# Power_PD.net
KiCad netlist of a schematic drawn in Altium Designer
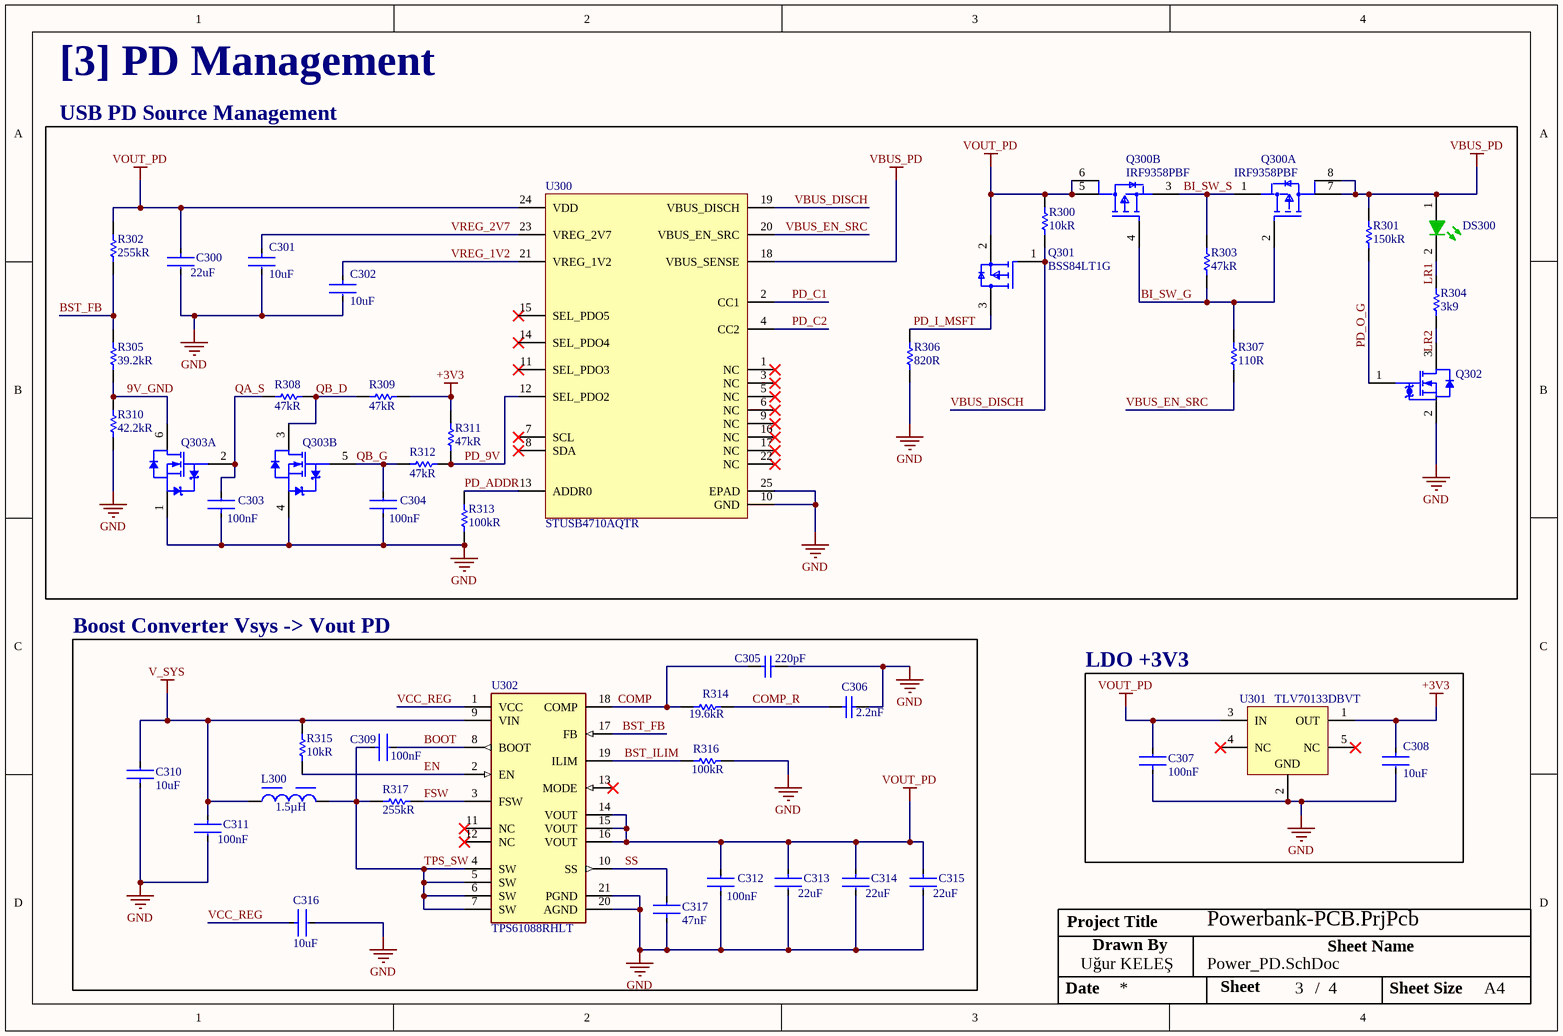
[diagram p0: Power_PD.SchDoc]

(export (version "E")
  (design (tool "Eeschema 10.0.6"))
  (components
    (comp (ref "C300")
      (value "GRT21BR61E226ME13L")
      (footprint "FP-GRT21B-0_2-IPC_C")
      (description "Multi-Layer Ceramic Capacitor 22uF 25V X5R ±20% 0805 Emboss T/R")
      (fields (field (name "CAPACITANCE") "22uF") (field (name "TOLERANCE") "20%"))
      (libsource (lib "Altium Content Vault") (part "02cd4be3c70576c341d710602a673aa"))
    )
    (comp (ref "C301")
      (value "GRM188R61E106MA73D")
      (footprint "FP-GRM188-0_2-MFG")
      (description "Chip Multilayer Ceramic Capacitors for General Purpose, 0603, 10uF, X5R, 15%, 20%, 25V")
      (fields
        (field (name "TOLERANCE") "20%")
        (field (name "VOLTAGE") "25V")
        (field (name "CAPACITANCE") "10uF")
      )
      (libsource (lib "Altium Content Vault") (part "11868f565c42a9108669ba33697ecf6"))
    )
    (comp (ref "C302")
      (value "GRM188R61E106MA73D")
      (footprint "FP-GRM188-0_2-MFG")
      (description "Chip Multilayer Ceramic Capacitors for General Purpose, 0603, 10uF, X5R, 15%, 20%, 25V")
      (fields
        (field (name "TOLERANCE") "20%")
        (field (name "VOLTAGE") "25V")
        (field (name "CAPACITANCE") "10uF")
      )
      (libsource (lib "Altium Content Vault") (part "11868f565c42a9108669ba33697ecf6"))
    )
    (comp (ref "C303")
      (value "GRM155R61H104KE19D")
      (footprint "FP-GRM155-0_05-IPC_A")
      (description "Chip Multilayer Ceramic Capacitors for General Purpose, 0402, 0.10uF, X5R, 15%, 10%, 50V")
      (fields
        (field (name "VOLTAGE") "50V")
        (field (name "TOLERANCE") "10%")
        (field (name "CAPACITANCE") "100nF")
      )
      (libsource (lib "Altium Content Vault") (part "02cd4be3c70576c341d710602a673aa"))
    )
    (comp (ref "C304")
      (value "GRM155R61H104KE19D")
      (footprint "FP-GRM155-0_05-IPC_A")
      (description "Chip Multilayer Ceramic Capacitors for General Purpose, 0402, 0.10uF, X5R, 15%, 10%, 50V")
      (fields
        (field (name "VOLTAGE") "50V")
        (field (name "TOLERANCE") "10%")
        (field (name "CAPACITANCE") "100nF")
      )
      (libsource (lib "Altium Content Vault") (part "02cd4be3c70576c341d710602a673aa"))
    )
    (comp (ref "C305")
      (value "220pF")
      (footprint "CAPC1005X55X25LL05T10")
      (fields (field (name "MANUFACTURER") "Murata") (field (name "PART NUMBER") "GRM155R71H221KA01D"))
      (libsource (lib "Altium Content Vault") (part "CAP"))
    )
    (comp (ref "C306")
      (value "2.2nF")
      (footprint "CAPC1005X55X25LL05T10")
      (fields (field (name "PART NUMBER") "GRM155R71E222KA01D") (field (name "MANUFACTURER") "Murata"))
      (libsource (lib "Altium Content Vault") (part "CAP"))
    )
    (comp (ref "C307")
      (value "GRM155R61H104KE19D")
      (footprint "FP-GRM155-0_05-IPC_A")
      (description "Chip Multilayer Ceramic Capacitors for General Purpose, 0402, 0.10uF, X5R, 15%, 10%, 50V")
      (fields
        (field (name "VOLTAGE") "50V")
        (field (name "TOLERANCE") "10%")
        (field (name "CAPACITANCE") "100nF")
      )
      (libsource (lib "Altium Content Vault") (part "02cd4be3c70576c341d710602a673aa"))
    )
    (comp (ref "C308")
      (value "GRM188R61E106MA73D")
      (footprint "FP-GRM188-0_2-MFG")
      (description "Chip Multilayer Ceramic Capacitors for General Purpose, 0603, 10uF, X5R, 15%, 20%, 25V")
      (fields
        (field (name "TOLERANCE") "20%")
        (field (name "VOLTAGE") "25V")
        (field (name "CAPACITANCE") "10uF")
      )
      (libsource (lib "Altium Content Vault") (part "11868f565c42a9108669ba33697ecf6"))
    )
    (comp (ref "C309")
      (value "GRM155R61H104KE19D")
      (footprint "FP-GRM155-0_05-IPC_A")
      (description "Chip Multilayer Ceramic Capacitors for General Purpose, 0402, 0.10uF, X5R, 15%, 10%, 50V")
      (fields
        (field (name "VOLTAGE") "50V")
        (field (name "TOLERANCE") "10%")
        (field (name "CAPACITANCE") "100nF")
      )
      (libsource (lib "Altium Content Vault") (part "02cd4be3c70576c341d710602a673aa"))
    )
    (comp (ref "C310")
      (value "GRM188R61E106MA73D")
      (footprint "FP-GRM188-0_2-MFG")
      (description "Chip Multilayer Ceramic Capacitors for General Purpose, 0603, 10uF, X5R, 15%, 20%, 25V")
      (fields
        (field (name "TOLERANCE") "20%")
        (field (name "VOLTAGE") "25V")
        (field (name "CAPACITANCE") "10uF")
      )
      (libsource (lib "Altium Content Vault") (part "11868f565c42a9108669ba33697ecf6"))
    )
    (comp (ref "C311")
      (value "GRM155R61H104KE19D")
      (footprint "FP-GRM155-0_05-IPC_A")
      (description "Chip Multilayer Ceramic Capacitors for General Purpose, 0402, 0.10uF, X5R, 15%, 10%, 50V")
      (fields
        (field (name "VOLTAGE") "50V")
        (field (name "TOLERANCE") "10%")
        (field (name "CAPACITANCE") "100nF")
      )
      (libsource (lib "Altium Content Vault") (part "02cd4be3c70576c341d710602a673aa"))
    )
    (comp (ref "C312")
      (value "GRM155R61H104KE19D")
      (footprint "FP-GRM155-0_05-IPC_A")
      (description "Chip Multilayer Ceramic Capacitors for General Purpose, 0402, 0.10uF, X5R, 15%, 10%, 50V")
      (fields
        (field (name "VOLTAGE") "50V")
        (field (name "TOLERANCE") "10%")
        (field (name "CAPACITANCE") "100nF")
      )
      (libsource (lib "Altium Content Vault") (part "02cd4be3c70576c341d710602a673aa"))
    )
    (comp (ref "C313")
      (value "GRT21BR61E226ME13L")
      (footprint "FP-GRT21B-0_2-IPC_C")
      (description "Multi-Layer Ceramic Capacitor 22uF 25V X5R ±20% 0805 Emboss T/R")
      (fields (field (name "CAPACITANCE") "22uF") (field (name "TOLERANCE") "20%"))
      (libsource (lib "Altium Content Vault") (part "02cd4be3c70576c341d710602a673aa"))
    )
    (comp (ref "C314")
      (value "GRT21BR61E226ME13L")
      (footprint "FP-GRT21B-0_2-IPC_C")
      (description "Multi-Layer Ceramic Capacitor 22uF 25V X5R ±20% 0805 Emboss T/R")
      (fields (field (name "CAPACITANCE") "22uF") (field (name "TOLERANCE") "20%"))
      (libsource (lib "Altium Content Vault") (part "02cd4be3c70576c341d710602a673aa"))
    )
    (comp (ref "C315")
      (value "GRT21BR61E226ME13L")
      (footprint "FP-GRT21B-0_2-IPC_C")
      (description "Multi-Layer Ceramic Capacitor 22uF 25V X5R ±20% 0805 Emboss T/R")
      (fields (field (name "CAPACITANCE") "22uF") (field (name "TOLERANCE") "20%"))
      (libsource (lib "Altium Content Vault") (part "02cd4be3c70576c341d710602a673aa"))
    )
    (comp (ref "C316")
      (value "GRM188R61E106MA73D")
      (footprint "FP-GRM188-0_2-MFG")
      (description "Chip Multilayer Ceramic Capacitors for General Purpose, 0603, 10uF, X5R, 15%, 20%, 25V")
      (fields
        (field (name "TOLERANCE") "20%")
        (field (name "VOLTAGE") "25V")
        (field (name "CAPACITANCE") "10uF")
      )
      (libsource (lib "Altium Content Vault") (part "11868f565c42a9108669ba33697ecf6"))
    )
    (comp (ref "C317")
      (value "GRM155R71E473KA88D")
      (footprint "FP-GRM155-0_05-MFG")
      (description "Chip Multilayer Ceramic Capacitors for General Purpose, 0402, 47000pF, X7R, 15%, 10%, 25V")
      (fields
        (field (name "CAPACITANCE") "47nF")
        (field (name "TOLERANCE") "10%")
        (field (name "VOLTAGE") "25V")
      )
      (libsource (lib "Altium Content Vault") (part "02cd4be3c70576c341d710602a673aa"))
    )
    (comp (ref "DS300")
      (value "KP-1608MGC")
      (footprint "KING-0603LED_GREEN_V")
      (description "LED, SMT, 0603(1608), 1.1mm thickness, Green")
      (fields (field (name "MANUFACTURER") "Kingbright"))
      (libsource (lib "Altium Content Vault") (part "KING-LED-GREEN-A1K2-2"))
    )
    (comp (ref "L300")
      (value "744311150")
      (footprint "WE-HCI_7040")
      (fields (field (name "INDUCTANCE") "1.5µH") (field (name "TOLERANCE") "20%"))
      (libsource (lib "Altium Content Vault") (part "Inductor - 3"))
    )
    (comp (ref "Q300")
      (value "IRF9358PBF")
      (footprint "FP-PG-DSO-8-MFG")
      (description "MOSFET 2P-CH 30V 9.2A 8SOIC")
      (fields
        (field (name "MANUFACTURER") "Infineon Technologies")
        (field (name "OCTOPART") "https://octopart.com/irf9358pbf-infineon-65873752")
      )
      (libsource (lib "Altium Content Vault") (part "fdcadba95356e2d4f2253b8ff3f3b8c"))
    )
    (comp (ref "Q301")
      (value "BSS84LT1G")
      (footprint "FP-318-08-IPC_A")
      (description "MOSFET P-CH 50V 130MA SOT-23")
      (libsource (lib "Altium Content Vault") (part "1317a8eff0fddff9cd18bdaa032127a"))
    )
    (comp (ref "Q302")
      (value "2N7002KT3G")
      (footprint "ONSC-SOT-23-3-318-08_V")
      (description "Small Signal MOSFET, 60 V, 380 mA, Single, N-Channel, 3-Pin SOT-23, Pb-Free, Tape and Reel")
      (fields (field (name "MANUFACTURER") "On Semiconductor"))
      (libsource (lib "Altium Content Vault") (part "ONSC-NMOS-G1S2D3-3_B"))
    )
    (comp (ref "Q303")
      (value "2N7002BKS,115")
      (footprint "NXP-SOT363_M")
      (description "Dual N-Channel Trench MOSFET, 60 V, 0.3 A, -55 to 150 degC, 6-Pin SOT363, Tape and Reel")
      (fields (field (name "MANUFACTURER") "NXP Semiconductors"))
      (libsource (lib "Altium Content Vault") (part "NXP-NNMOS-SGDSGD-6_A"))
    )
    (comp (ref "R300")
      (value "10kR")
      (footprint "RESC1005X40X25ML05T10")
      (fields
        (field (name "PART NUMBER") "CRCW040210K0FKEDHP")
        (field (name "MANUFACTURER") "Vishay Dale")
        (field (name "TOLERANCE") "1%")
      )
      (libsource (lib "Altium Content Vault") (part "RES"))
    )
    (comp (ref "R301")
      (value "150kR")
      (footprint "RESC1609X50X30ML10T20")
      (fields
        (field (name "PART NUMBER") "CRCW0603150KFKTA")
        (field (name "MANUFACTURER") "Vishay Dale")
        (field (name "TOLERANCE") "1%")
      )
      (libsource (lib "Altium Content Vault") (part "RES"))
    )
    (comp (ref "R302")
      (value "255kR")
      (footprint "RESC1005X40X25ML05T05")
      (fields
        (field (name "MANUFACTURER") "Vishay Dale")
        (field (name "PART NUMBER") "CRCW0402255KFKED")
        (field (name "TOLERANCE") "1%")
      )
      (libsource (lib "Altium Content Vault") (part "RES"))
    )
    (comp (ref "R303")
      (value "47kR")
      (footprint "RESC1005X40X25ML05T10")
      (fields
        (field (name "PART NUMBER") "CRCW040247K0FKEDHP")
        (field (name "MANUFACTURER") "Vishay Dale")
        (field (name "TOLERANCE") "1%")
      )
      (libsource (lib "Altium Content Vault") (part "RES"))
    )
    (comp (ref "R304")
      (value "3k9")
      (footprint "RESC0603(1608)_N")
      (description "3K9 0.1W 5% 0603 (1608 Metric)  SMD")
      (fields (field (name "POWER") "0.1 W") (field (name "TOLERANCE") "5 %"))
      (libsource (lib "Altium Content Vault") (part "RES"))
    )
    (comp (ref "R305")
      (value "39.2kR")
      (footprint "RESC1005X40X25NL05T05")
      (fields
        (field (name "MANUFACTURER") "Vishay Dale")
        (field (name "PART NUMBER") "CRCW040239K2FKED")
        (field (name "TOLERANCE") "1%")
      )
      (libsource (lib "Altium Content Vault") (part "RES"))
    )
    (comp (ref "R306")
      (value "820R")
      (footprint "RESC0603(1608)_M")
      (description "820R 0.1W 1% 0603 (1608 Metric)  SMD")
      (fields (field (name "TOLERANCE") "1 %") (field (name "POWER") "0.1 W"))
      (libsource (lib "Altium Content Vault") (part "RES"))
    )
    (comp (ref "R307")
      (value "110R")
      (footprint "RESC1005X40X25NL05T05")
      (fields
        (field (name "PART NUMBER") "CRCW0402110RFKTD")
        (field (name "MANUFACTURER") "Vishay Dale")
        (field (name "TOLERANCE") "1%")
      )
      (libsource (lib "Altium Content Vault") (part "RES"))
    )
    (comp (ref "R308")
      (value "47kR")
      (footprint "RESC1005X40X25ML05T10")
      (fields
        (field (name "PART NUMBER") "CRCW040247K0FKEDHP")
        (field (name "MANUFACTURER") "Vishay Dale")
        (field (name "TOLERANCE") "1%")
      )
      (libsource (lib "Altium Content Vault") (part "RES"))
    )
    (comp (ref "R309")
      (value "47kR")
      (footprint "RESC1005X40X25ML05T10")
      (fields
        (field (name "PART NUMBER") "CRCW040247K0FKEDHP")
        (field (name "MANUFACTURER") "Vishay Dale")
        (field (name "TOLERANCE") "1%")
      )
      (libsource (lib "Altium Content Vault") (part "RES"))
    )
    (comp (ref "R310")
      (value "42.2kR")
      (footprint "RESC1005X40X25ML05T05")
      (fields
        (field (name "PART NUMBER") "CRCW040242K2FKED")
        (field (name "MANUFACTURER") "Vishay Dale")
        (field (name "TOLERANCE") "1%")
      )
      (libsource (lib "Altium Content Vault") (part "RES"))
    )
    (comp (ref "R311")
      (value "47kR")
      (footprint "RESC1005X40X25ML05T10")
      (fields
        (field (name "PART NUMBER") "CRCW040247K0FKEDHP")
        (field (name "MANUFACTURER") "Vishay Dale")
        (field (name "TOLERANCE") "1%")
      )
      (libsource (lib "Altium Content Vault") (part "RES"))
    )
    (comp (ref "R312")
      (value "47kR")
      (footprint "RESC1005X40X25ML05T10")
      (fields
        (field (name "PART NUMBER") "CRCW040247K0FKEDHP")
        (field (name "MANUFACTURER") "Vishay Dale")
        (field (name "TOLERANCE") "1%")
      )
      (libsource (lib "Altium Content Vault") (part "RES"))
    )
    (comp (ref "R313")
      (value "100kR")
      (footprint "RESC1609X50X30ML10T20")
      (fields
        (field (name "MANUFACTURER") "Vishay Dale")
        (field (name "PART NUMBER") "CRCW0603100KFKEB")
        (field (name "TOLERANCE") "1%")
      )
      (libsource (lib "Altium Content Vault") (part "RES"))
    )
    (comp (ref "R314")
      (value "19.6kR")
      (footprint "RESC1005X40X25NL05T05")
      (fields
        (field (name "PART NUMBER") "CRCW040219K6FKED")
        (field (name "MANUFACTURER") "Vishay Dale")
        (field (name "TOLERANCE") "1%")
      )
      (libsource (lib "Altium Content Vault") (part "RES"))
    )
    (comp (ref "R315")
      (value "10kR")
      (footprint "RESC1005X40X25ML05T10")
      (fields
        (field (name "PART NUMBER") "CRCW040210K0FKEDHP")
        (field (name "MANUFACTURER") "Vishay Dale")
        (field (name "TOLERANCE") "1%")
      )
      (libsource (lib "Altium Content Vault") (part "RES"))
    )
    (comp (ref "R316")
      (value "100kR")
      (footprint "RESC1609X50X30ML10T20")
      (fields
        (field (name "MANUFACTURER") "Vishay Dale")
        (field (name "PART NUMBER") "CRCW0603100KFKEB")
        (field (name "TOLERANCE") "1%")
      )
      (libsource (lib "Altium Content Vault") (part "RES"))
    )
    (comp (ref "R317")
      (value "255kR")
      (footprint "RESC1005X40X25ML05T05")
      (fields
        (field (name "MANUFACTURER") "Vishay Dale")
        (field (name "PART NUMBER") "CRCW0402255KFKED")
        (field (name "TOLERANCE") "1%")
      )
      (libsource (lib "Altium Content Vault") (part "RES"))
    )
    (comp (ref "U300")
      (value "STUSB4710AQTR")
      (footprint "QFN24EP_4X4_STM")
      (description "Power Supply Support Circuit, Adjustable, 2 Channel, 0.2")
      (fields (field (name "MANUFACTURER") "STMicroelectronics"))
      (libsource (lib "UDEMY_Library") (part "STUSB4710AQTR"))
    )
    (comp (ref "U301")
      (value "TLV70133DBVT")
      (footprint "DBV0005A_M")
      (fields (field (name "MANUFACTURER") "Texas Instruments"))
      (libsource (lib "Altium Content Vault") (part "TI-TLV7013XDBV5"))
    )
    (comp (ref "U302")
      (value "TPS61088RHLT")
      (footprint "FP-RHL0020A-MFG")
      (description "IC REG BOOST ADJ 10A 20VQFN")
      (fields
        (field (name "OCTOPART") "https://octopart.com/tps61088rhlt-texas+instruments-57155059")
        (field (name "MANUFACTURER") "Texas Instruments")
      )
      (libsource (lib "Altium Content Vault") (part "866d791168d43c93e8e886550da2fd8"))
    )
  )
  (nets
    (net (code "1") (name "+3V3") (class "Default")
      (node (ref "C308") (pin "1") (pinfunction "1_1") (pintype "passive"))
      (node (ref "R309") (pin "1") (pinfunction "1_1") (pintype "passive"))
      (node (ref "R311") (pin "2") (pinfunction "2_2") (pintype "passive"))
      (node (ref "U301") (pin "1") (pinfunction "OUT_1") (pintype "power_in"))
    )
    (net (code "2") (name "/9V_GND") (class "Default")
      (node (ref "Q303") (pin "6") (pinfunction "D1_6") (pintype "passive"))
      (node (ref "R305") (pin "1") (pinfunction "1_1") (pintype "passive"))
      (node (ref "R310") (pin "2") (pinfunction "2_2") (pintype "passive"))
    )
    (net (code "3") (name "/BI_SW_G") (class "Default")
      (node (ref "Q300") (pin "2") (pinfunction "G2_2") (pintype "passive"))
      (node (ref "Q300") (pin "4") (pinfunction "G1_4") (pintype "passive"))
      (node (ref "R303") (pin "1") (pinfunction "1_1") (pintype "passive"))
      (node (ref "R307") (pin "2") (pinfunction "2_2") (pintype "passive"))
    )
    (net (code "4") (name "/BI_SW_S") (class "Default")
      (node (ref "Q300") (pin "1") (pinfunction "S2_1") (pintype "passive"))
      (node (ref "Q300") (pin "3") (pinfunction "S1_3") (pintype "passive"))
      (node (ref "R303") (pin "2") (pinfunction "2_2") (pintype "passive"))
    )
    (net (code "5") (name "/BOOT") (class "Default")
      (node (ref "C309") (pin "2") (pinfunction "2_2") (pintype "passive"))
      (node (ref "U302") (pin "8") (pinfunction "BOOT_8") (pintype "output"))
    )
    (net (code "6") (name "/BST_FB") (class "Default")
      (node (ref "R302") (pin "1") (pinfunction "1_1") (pintype "passive"))
      (node (ref "R305") (pin "2") (pinfunction "2_2") (pintype "passive"))
      (node (ref "U302") (pin "17") (pinfunction "FB_17") (pintype "input"))
    )
    (net (code "7") (name "/BST_ILIM") (class "Default")
      (node (ref "R316") (pin "1") (pinfunction "1_1") (pintype "passive"))
      (node (ref "U302") (pin "19") (pinfunction "ILIM_19") (pintype "passive"))
    )
    (net (code "8") (name "/COMP") (class "Default")
      (node (ref "C305") (pin "1") (pinfunction "1_1") (pintype "passive"))
      (node (ref "R314") (pin "1") (pinfunction "1_1") (pintype "passive"))
      (node (ref "U302") (pin "18") (pinfunction "COMP_18") (pintype "passive"))
    )
    (net (code "9") (name "/COMP_R") (class "Default")
      (node (ref "C306") (pin "1") (pinfunction "1_1") (pintype "passive"))
      (node (ref "R314") (pin "2") (pinfunction "2_2") (pintype "passive"))
    )
    (net (code "10") (name "/EN") (class "Default")
      (node (ref "R315") (pin "2") (pinfunction "2_2") (pintype "passive"))
      (node (ref "U302") (pin "2") (pinfunction "EN_2") (pintype "input"))
    )
    (net (code "11") (name "/FSW") (class "Default")
      (node (ref "R317") (pin "2") (pinfunction "2_2") (pintype "passive"))
      (node (ref "U302") (pin "3") (pinfunction "FSW_3") (pintype "passive"))
    )
    (net (code "12") (name "/LR1") (class "Default")
      (node (ref "DS300") (pin "2") (pinfunction "K_2") (pintype "passive"))
      (node (ref "R304") (pin "2") (pinfunction "2_2") (pintype "passive"))
    )
    (net (code "13") (name "/LR2") (class "Default")
      (node (ref "Q302") (pin "3") (pinfunction "D_3") (pintype "passive"))
      (node (ref "R304") (pin "1") (pinfunction "1_1") (pintype "passive"))
    )
    (net (code "14") (name "/PD_9V") (class "Default")
      (node (ref "R311") (pin "1") (pinfunction "1_1") (pintype "passive"))
      (node (ref "R312") (pin "1") (pinfunction "1_1") (pintype "passive"))
      (node (ref "U300") (pin "12") (pinfunction "SEL_PDO2_12") (pintype "passive"))
    )
    (net (code "15") (name "/PD_ADDR") (class "Default")
      (node (ref "R313") (pin "2") (pinfunction "2_2") (pintype "passive"))
      (node (ref "U300") (pin "13") (pinfunction "ADDR0_13") (pintype "passive"))
    )
    (net (code "16") (name "/PD_C1") (class "Default")
      (node (ref "U300") (pin "2") (pinfunction "CC1_2") (pintype "passive"))
    )
    (net (code "17") (name "/PD_C2") (class "Default")
      (node (ref "U300") (pin "4") (pinfunction "CC2_4") (pintype "passive"))
    )
    (net (code "18") (name "/PD_I_MSFT") (class "Default")
      (node (ref "Q301") (pin "3") (pinfunction "D_3") (pintype "passive"))
      (node (ref "R306") (pin "2") (pinfunction "2_2") (pintype "passive"))
    )
    (net (code "19") (name "/PD_O_G") (class "Default")
      (node (ref "Q302") (pin "1") (pinfunction "G_1") (pintype "passive"))
      (node (ref "R301") (pin "2") (pinfunction "2_2") (pintype "passive"))
    )
    (net (code "20") (name "/QA_S") (class "Default")
      (node (ref "C303") (pin "2") (pinfunction "2_2") (pintype "passive"))
      (node (ref "Q303") (pin "2") (pinfunction "G1_2") (pintype "passive"))
      (node (ref "R308") (pin "2") (pinfunction "2_2") (pintype "passive"))
    )
    (net (code "21") (name "/QB_D") (class "Default")
      (node (ref "Q303") (pin "3") (pinfunction "D2_3") (pintype "passive"))
      (node (ref "R308") (pin "1") (pinfunction "1_1") (pintype "passive"))
      (node (ref "R309") (pin "2") (pinfunction "2_2") (pintype "passive"))
    )
    (net (code "22") (name "/QB_G") (class "Default")
      (node (ref "C304") (pin "2") (pinfunction "2_2") (pintype "passive"))
      (node (ref "Q303") (pin "5") (pinfunction "G2_5") (pintype "passive"))
      (node (ref "R312") (pin "2") (pinfunction "2_2") (pintype "passive"))
    )
    (net (code "23") (name "/SS") (class "Default")
      (node (ref "C317") (pin "2") (pinfunction "2_2") (pintype "passive"))
      (node (ref "U302") (pin "10") (pinfunction "SS_10") (pintype "output"))
    )
    (net (code "24") (name "/TPS_SW") (class "Default")
      (node (ref "C309") (pin "1") (pinfunction "1_1") (pintype "passive"))
      (node (ref "L300") (pin "2") (pinfunction "2_2") (pintype "passive"))
      (node (ref "R317") (pin "1") (pinfunction "1_1") (pintype "passive"))
      (node (ref "U302") (pin "4") (pinfunction "SW_4") (pintype "power_in"))
      (node (ref "U302") (pin "5") (pinfunction "SW_5") (pintype "power_in"))
      (node (ref "U302") (pin "6") (pinfunction "SW_6") (pintype "power_in"))
      (node (ref "U302") (pin "7") (pinfunction "SW_7") (pintype "power_in"))
    )
    (net (code "25") (name "/VBUS_DISCH") (class "Default")
      (node (ref "Q301") (pin "1") (pinfunction "G_1") (pintype "passive"))
      (node (ref "R300") (pin "2") (pinfunction "2_2") (pintype "passive"))
      (node (ref "U300") (pin "19") (pinfunction "VBUS_DISCH_19") (pintype "passive"))
    )
    (net (code "26") (name "/VBUS_EN_SRC") (class "Default")
      (node (ref "R307") (pin "1") (pinfunction "1_1") (pintype "passive"))
      (node (ref "U300") (pin "20") (pinfunction "VBUS_EN_SRC_20") (pintype "passive"))
    )
    (net (code "27") (name "/VCC_REG") (class "Default")
      (node (ref "C316") (pin "1") (pinfunction "1_1") (pintype "passive"))
      (node (ref "U302") (pin "1") (pinfunction "VCC_1") (pintype "power_in"))
    )
    (net (code "28") (name "/VREG_1V2") (class "Default")
      (node (ref "C302") (pin "1") (pinfunction "1_1") (pintype "passive"))
      (node (ref "U300") (pin "21") (pinfunction "VREG_1V2_21") (pintype "passive"))
    )
    (net (code "29") (name "/VREG_2V7") (class "Default")
      (node (ref "C301") (pin "1") (pinfunction "1_1") (pintype "passive"))
      (node (ref "U300") (pin "23") (pinfunction "VREG_2V7_23") (pintype "passive"))
    )
    (net (code "30") (name "GND") (class "Default")
      (node (ref "C300") (pin "2") (pinfunction "2_2") (pintype "passive"))
      (node (ref "C301") (pin "2") (pinfunction "2_2") (pintype "passive"))
      (node (ref "C302") (pin "2") (pinfunction "2_2") (pintype "passive"))
      (node (ref "C303") (pin "1") (pinfunction "1_1") (pintype "passive"))
      (node (ref "C304") (pin "1") (pinfunction "1_1") (pintype "passive"))
      (node (ref "C305") (pin "2") (pinfunction "2_2") (pintype "passive"))
      (node (ref "C306") (pin "2") (pinfunction "2_2") (pintype "passive"))
      (node (ref "C307") (pin "1") (pinfunction "1_1") (pintype "passive"))
      (node (ref "C308") (pin "2") (pinfunction "2_2") (pintype "passive"))
      (node (ref "C310") (pin "1") (pinfunction "1_1") (pintype "passive"))
      (node (ref "C311") (pin "2") (pinfunction "2_2") (pintype "passive"))
      (node (ref "C312") (pin "1") (pinfunction "1_1") (pintype "passive"))
      (node (ref "C313") (pin "2") (pinfunction "2_2") (pintype "passive"))
      (node (ref "C314") (pin "2") (pinfunction "2_2") (pintype "passive"))
      (node (ref "C315") (pin "2") (pinfunction "2_2") (pintype "passive"))
      (node (ref "C316") (pin "2") (pinfunction "2_2") (pintype "passive"))
      (node (ref "C317") (pin "1") (pinfunction "1_1") (pintype "passive"))
      (node (ref "Q302") (pin "2") (pinfunction "S_2") (pintype "passive"))
      (node (ref "Q303") (pin "1") (pinfunction "S1_1") (pintype "passive"))
      (node (ref "Q303") (pin "4") (pinfunction "S2_4") (pintype "passive"))
      (node (ref "R306") (pin "1") (pinfunction "1_1") (pintype "passive"))
      (node (ref "R310") (pin "1") (pinfunction "1_1") (pintype "passive"))
      (node (ref "R313") (pin "1") (pinfunction "1_1") (pintype "passive"))
      (node (ref "R316") (pin "2") (pinfunction "2_2") (pintype "passive"))
      (node (ref "U300") (pin "10") (pinfunction "GND_10") (pintype "passive"))
      (node (ref "U300") (pin "25") (pinfunction "EPAD_25") (pintype "passive"))
      (node (ref "U301") (pin "2") (pinfunction "GND_2") (pintype "power_in"))
      (node (ref "U302") (pin "20") (pinfunction "AGND_20") (pintype "power_in"))
      (node (ref "U302") (pin "21") (pinfunction "PGND_21") (pintype "power_in"))
    )
    (net (code "31") (name "VBUS_PD") (class "Default")
      (node (ref "DS300") (pin "1") (pinfunction "A_1") (pintype "passive"))
      (node (ref "Q300") (pin "7") (pinfunction "D2_7") (pintype "passive"))
      (node (ref "Q300") (pin "8") (pinfunction "D2_8") (pintype "passive"))
      (node (ref "R301") (pin "1") (pinfunction "1_1") (pintype "passive"))
      (node (ref "U300") (pin "18") (pinfunction "VBUS_SENSE_18") (pintype "passive"))
    )
    (net (code "32") (name "VOUT_PD") (class "Default")
      (node (ref "C300") (pin "1") (pinfunction "1_1") (pintype "passive"))
      (node (ref "C307") (pin "2") (pinfunction "2_2") (pintype "passive"))
      (node (ref "C312") (pin "2") (pinfunction "2_2") (pintype "passive"))
      (node (ref "C313") (pin "1") (pinfunction "1_1") (pintype "passive"))
      (node (ref "C314") (pin "1") (pinfunction "1_1") (pintype "passive"))
      (node (ref "C315") (pin "1") (pinfunction "1_1") (pintype "passive"))
      (node (ref "Q300") (pin "5") (pinfunction "D1_5") (pintype "passive"))
      (node (ref "Q300") (pin "6") (pinfunction "D1_6") (pintype "passive"))
      (node (ref "Q301") (pin "2") (pinfunction "S_2") (pintype "passive"))
      (node (ref "R300") (pin "1") (pinfunction "1_1") (pintype "passive"))
      (node (ref "R302") (pin "2") (pinfunction "2_2") (pintype "passive"))
      (node (ref "U300") (pin "24") (pinfunction "VDD_24") (pintype "passive"))
      (node (ref "U301") (pin "3") (pinfunction "IN_3") (pintype "power_in"))
      (node (ref "U302") (pin "14") (pinfunction "VOUT_14") (pintype "power_in"))
      (node (ref "U302") (pin "15") (pinfunction "VOUT_15") (pintype "power_in"))
      (node (ref "U302") (pin "16") (pinfunction "VOUT_16") (pintype "power_in"))
    )
    (net (code "33") (name "V_SYS") (class "Default")
      (node (ref "C310") (pin "2") (pinfunction "2_2") (pintype "passive"))
      (node (ref "C311") (pin "1") (pinfunction "1_1") (pintype "passive"))
      (node (ref "L300") (pin "1") (pinfunction "1_1") (pintype "passive"))
      (node (ref "R315") (pin "1") (pinfunction "1_1") (pintype "passive"))
      (node (ref "U302") (pin "9") (pinfunction "VIN_9") (pintype "power_in"))
    )
    (net (code "34") (name "unconnected-(U300-NC-Pad1)") (class "Default")
      (node (ref "U300") (pin "1") (pinfunction "NC_1") (pintype "passive+no_connect"))
    )
    (net (code "35") (name "unconnected-(U300-NC-Pad3)") (class "Default")
      (node (ref "U300") (pin "3") (pinfunction "NC_3") (pintype "passive+no_connect"))
    )
    (net (code "36") (name "unconnected-(U300-NC-Pad5)") (class "Default")
      (node (ref "U300") (pin "5") (pinfunction "NC_5") (pintype "passive+no_connect"))
    )
    (net (code "37") (name "unconnected-(U300-NC-Pad6)") (class "Default")
      (node (ref "U300") (pin "6") (pinfunction "NC_6") (pintype "passive+no_connect"))
    )
    (net (code "38") (name "unconnected-(U300-NC-Pad9)") (class "Default")
      (node (ref "U300") (pin "9") (pinfunction "NC_9") (pintype "passive+no_connect"))
    )
    (net (code "39") (name "unconnected-(U300-NC-Pad16)") (class "Default")
      (node (ref "U300") (pin "16") (pinfunction "NC_16") (pintype "passive+no_connect"))
    )
    (net (code "40") (name "unconnected-(U300-NC-Pad17)") (class "Default")
      (node (ref "U300") (pin "17") (pinfunction "NC_17") (pintype "passive+no_connect"))
    )
    (net (code "41") (name "unconnected-(U300-NC-Pad22)") (class "Default")
      (node (ref "U300") (pin "22") (pinfunction "NC_22") (pintype "passive+no_connect"))
    )
    (net (code "42") (name "unconnected-(U300-SCL-Pad7)") (class "Default")
      (node (ref "U300") (pin "7") (pinfunction "SCL_7") (pintype "passive+no_connect"))
    )
    (net (code "43") (name "unconnected-(U300-SDA-Pad8)") (class "Default")
      (node (ref "U300") (pin "8") (pinfunction "SDA_8") (pintype "passive+no_connect"))
    )
    (net (code "44") (name "unconnected-(U300-SEL_PDO3-Pad11)") (class "Default")
      (node (ref "U300") (pin "11") (pinfunction "SEL_PDO3_11") (pintype "passive+no_connect"))
    )
    (net (code "45") (name "unconnected-(U300-SEL_PDO4-Pad14)") (class "Default")
      (node (ref "U300") (pin "14") (pinfunction "SEL_PDO4_14") (pintype "passive+no_connect"))
    )
    (net (code "46") (name "unconnected-(U300-SEL_PDO5-Pad15)") (class "Default")
      (node (ref "U300") (pin "15") (pinfunction "SEL_PDO5_15") (pintype "passive+no_connect"))
    )
    (net (code "47") (name "unconnected-(U301-NC-Pad4)") (class "Default")
      (node (ref "U301") (pin "4") (pinfunction "NC_4") (pintype "passive+no_connect"))
    )
    (net (code "48") (name "unconnected-(U301-NC-Pad5)") (class "Default")
      (node (ref "U301") (pin "5") (pinfunction "NC_5") (pintype "passive+no_connect"))
    )
    (net (code "49") (name "unconnected-(U302-MODE-Pad13)") (class "Default")
      (node (ref "U302") (pin "13") (pinfunction "MODE_13") (pintype "input+no_connect"))
    )
    (net (code "50") (name "unconnected-(U302-NC-Pad11)") (class "Default")
      (node (ref "U302") (pin "11") (pinfunction "NC_11") (pintype "passive+no_connect"))
    )
    (net (code "51") (name "unconnected-(U302-NC-Pad12)") (class "Default")
      (node (ref "U302") (pin "12") (pinfunction "NC_12") (pintype "passive+no_connect"))
    )
  )
)
